# weightmeter.net
KiCad netlist of a schematic drawn in EAGLE
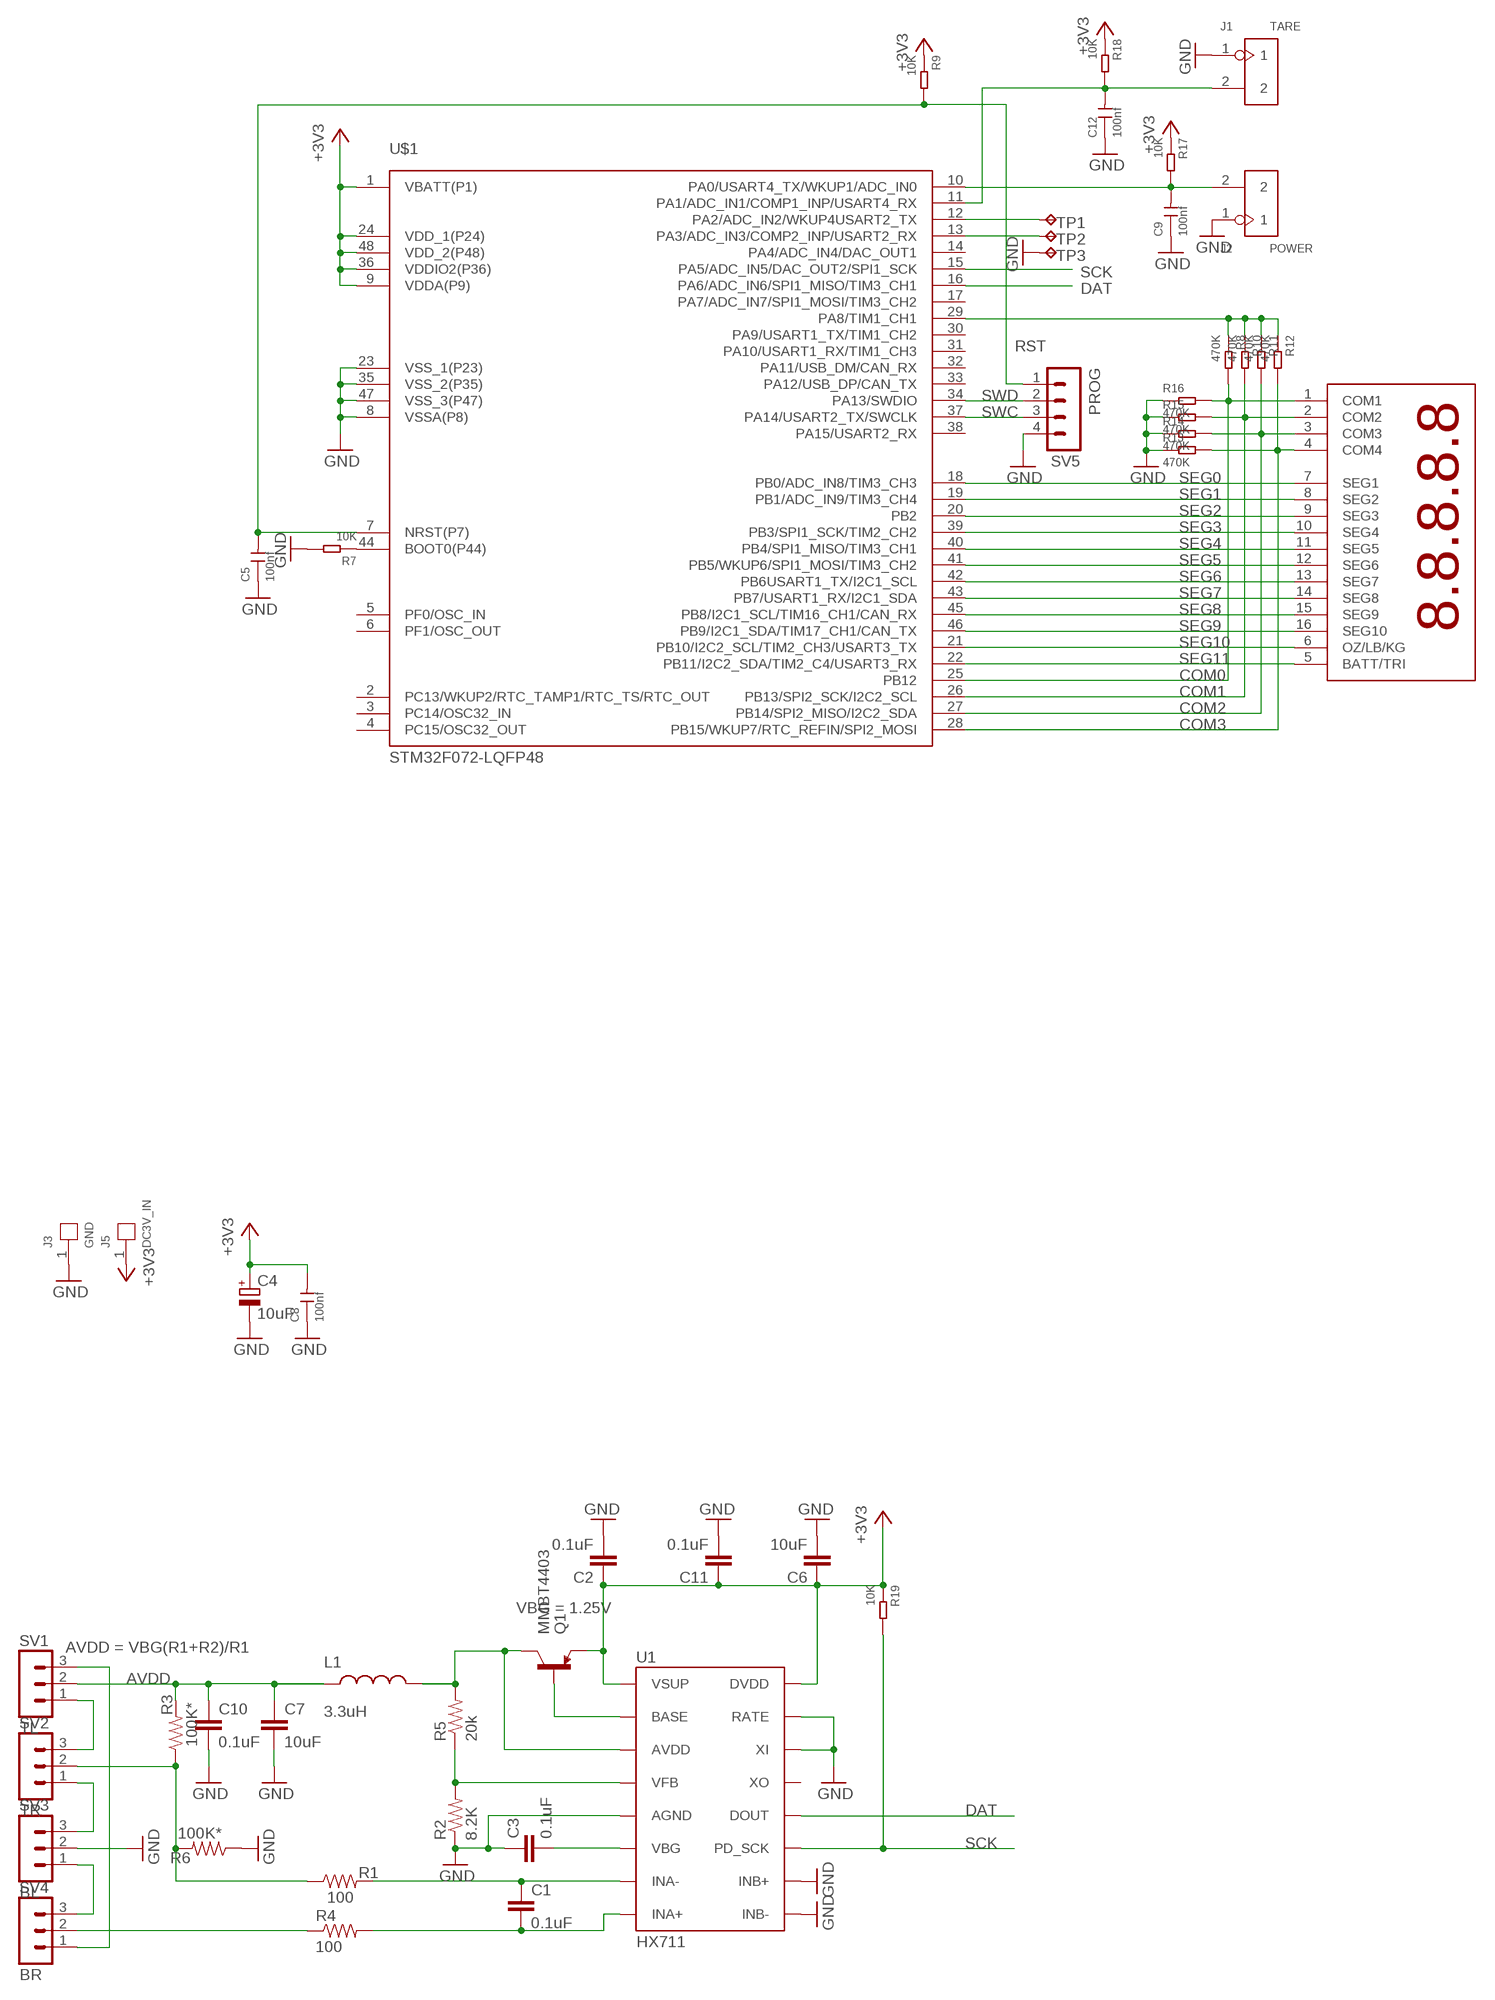
[diagram p0: schematic, sheet 1]

(export (version "E")
  (design (tool "Eeschema 10.0.6"))
  (components
    (comp (ref "C1")
      (value "0.1uF")
      (footprint "eagle-import:0603-CAP")
      (libsource (lib "eagle-import") (part "0.1UF-25V-5%(0603)"))
    )
    (comp (ref "C2")
      (value "0.1uF")
      (footprint "eagle-import:0603-CAP")
      (libsource (lib "eagle-import") (part "0.1UF-25V-5%(0603)"))
    )
    (comp (ref "C3")
      (value "0.1uF")
      (footprint "eagle-import:0603-CAP")
      (libsource (lib "eagle-import") (part "0.1UF-25V-5%(0603)"))
    )
    (comp (ref "C4")
      (value "10uF")
      (footprint "eagle-import:A_3216-18R")
      (libsource (lib "eagle-import") (part "CPOL-EUA/3216-18R"))
    )
    (comp (ref "C5")
      (value "100nf")
      (footprint "eagle-import:C0805")
      (fields (field (name "MPN") "CC0805KRX7R9BB104"))
      (libsource (lib "eagle-import") (part "CERAMIC-100NF-50V-10%-X7R(0805)"))
    )
    (comp (ref "C6")
      (value "10uF")
      (footprint "eagle-import:1210")
      (libsource (lib "eagle-import") (part "10UF50V20%(1210)"))
    )
    (comp (ref "C7")
      (value "10uF")
      (footprint "eagle-import:1210")
      (libsource (lib "eagle-import") (part "10UF50V20%(1210)"))
    )
    (comp (ref "C8")
      (value "100nf")
      (footprint "eagle-import:C0805")
      (fields (field (name "MPN") "CC0805KRX7R9BB104"))
      (libsource (lib "eagle-import") (part "CERAMIC-100NF-50V-10%-X7R(0805)"))
    )
    (comp (ref "C9")
      (value "100nf")
      (footprint "eagle-import:C0805")
      (fields (field (name "MPN") "CC0805KRX7R9BB104"))
      (libsource (lib "eagle-import") (part "CERAMIC-100NF-50V-10%-X7R(0805)"))
    )
    (comp (ref "C10")
      (value "0.1uF")
      (footprint "eagle-import:0603-CAP")
      (libsource (lib "eagle-import") (part "0.1UF-25V-5%(0603)"))
    )
    (comp (ref "C11")
      (value "0.1uF")
      (footprint "eagle-import:0603-CAP")
      (libsource (lib "eagle-import") (part "0.1UF-25V-5%(0603)"))
    )
    (comp (ref "C12")
      (value "100nf")
      (footprint "eagle-import:C0805")
      (fields (field (name "MPN") "CC0805KRX7R9BB104"))
      (libsource (lib "eagle-import") (part "CERAMIC-100NF-50V-10%-X7R(0805)"))
    )
    (comp (ref "J1")
      (value "TARE")
      (footprint "eagle-import:H2-2.54")
      (fields (field (name "MPN") "F185-1102A1BSYA1"))
      (libsource (lib "eagle-import") (part "DIP-BLACK-FEMALE-HEADER-VERT(2P-2.54)"))
    )
    (comp (ref "J2")
      (value "POWER")
      (footprint "eagle-import:H2-2.54")
      (fields (field (name "MPN") "F185-1102A1BSYA1"))
      (libsource (lib "eagle-import") (part "DIP-BLACK-FEMALE-HEADER-VERT(2P-2.54)"))
    )
    (comp (ref "J3")
      (value "GND")
      (footprint "eagle-import:1P-65_35MIL")
      (fields (field (name "MPN") "RF130-1013BBS0741"))
      (libsource (lib "eagle-import") (part "DIP-BLACK-ROUND-FEMALE-HEADER-VERT(1P-2.54)"))
    )
    (comp (ref "J5")
      (value "DC3V_IN")
      (footprint "eagle-import:1P-65_35MIL")
      (fields (field (name "MPN") "RF130-1013BBS0741"))
      (libsource (lib "eagle-import") (part "DIP-BLACK-ROUND-FEMALE-HEADER-VERT(1P-2.54)"))
    )
    (comp (ref "L1")
      (value "3.3uH")
      (footprint "eagle-import:0805")
      (libsource (lib "eagle-import") (part "INDUCTOR0805-IND"))
    )
    (comp (ref "Q1")
      (value "MMBT4403")
      (footprint "eagle-import:SOT23-3")
      (libsource (lib "eagle-import") (part "TRANSISTOR_PNPMMBT4403"))
    )
    (comp (ref "R1")
      (value "100")
      (footprint "eagle-import:0603-RES")
      (libsource (lib "eagle-import") (part "100OHM-1/10W-1%(0603)"))
    )
    (comp (ref "R2")
      (value "8.2K")
      (footprint "eagle-import:0603-RES")
      (libsource (lib "eagle-import") (part "8.2KOHM-1/10W-5%(0603)"))
    )
    (comp (ref "R3")
      (value "100K*")
      (footprint "eagle-import:0603-RES")
      (libsource (lib "eagle-import") (part "100OHM-1/10W-1%(0603)"))
    )
    (comp (ref "R4")
      (value "100")
      (footprint "eagle-import:0603-RES")
      (libsource (lib "eagle-import") (part "100OHM-1/10W-1%(0603)"))
    )
    (comp (ref "R5")
      (value "20k")
      (footprint "eagle-import:0603-RES")
      (libsource (lib "eagle-import") (part "20KOHM1/10W1%(0603)"))
    )
    (comp (ref "R6")
      (value "100K*")
      (footprint "eagle-import:0603-RES")
      (libsource (lib "eagle-import") (part "100OHM-1/10W-1%(0603)"))
    )
    (comp (ref "R7")
      (value "10K")
      (footprint "eagle-import:R0805")
      (fields (field (name "MPN") "RC0805JR-070RL"))
      (libsource (lib "eagle-import") (part "SMD-RES-0R-5%-1/8W(0805)"))
    )
    (comp (ref "R8")
      (value "470K")
      (footprint "eagle-import:R0805")
      (fields (field (name "MPN") "RC0805JR-070RL"))
      (libsource (lib "eagle-import") (part "SMD-RES-0R-5%-1/8W(0805)"))
    )
    (comp (ref "R9")
      (value "10K")
      (footprint "eagle-import:R0805")
      (fields (field (name "MPN") "RC0805JR-070RL"))
      (libsource (lib "eagle-import") (part "SMD-RES-0R-5%-1/8W(0805)"))
    )
    (comp (ref "R10")
      (value "470K")
      (footprint "eagle-import:R0805")
      (fields (field (name "MPN") "RC0805JR-070RL"))
      (libsource (lib "eagle-import") (part "SMD-RES-0R-5%-1/8W(0805)"))
    )
    (comp (ref "R11")
      (value "470K")
      (footprint "eagle-import:R0805")
      (fields (field (name "MPN") "RC0805JR-070RL"))
      (libsource (lib "eagle-import") (part "SMD-RES-0R-5%-1/8W(0805)"))
    )
    (comp (ref "R12")
      (value "470K")
      (footprint "eagle-import:R0805")
      (fields (field (name "MPN") "RC0805JR-070RL"))
      (libsource (lib "eagle-import") (part "SMD-RES-0R-5%-1/8W(0805)"))
    )
    (comp (ref "R13")
      (value "470K")
      (footprint "eagle-import:R0805")
      (fields (field (name "MPN") "RC0805JR-070RL"))
      (libsource (lib "eagle-import") (part "SMD-RES-0R-5%-1/8W(0805)"))
    )
    (comp (ref "R14")
      (value "470K")
      (footprint "eagle-import:R0805")
      (fields (field (name "MPN") "RC0805JR-070RL"))
      (libsource (lib "eagle-import") (part "SMD-RES-0R-5%-1/8W(0805)"))
    )
    (comp (ref "R15")
      (value "470K")
      (footprint "eagle-import:R0805")
      (fields (field (name "MPN") "RC0805JR-070RL"))
      (libsource (lib "eagle-import") (part "SMD-RES-0R-5%-1/8W(0805)"))
    )
    (comp (ref "R16")
      (value "470K")
      (footprint "eagle-import:R0805")
      (fields (field (name "MPN") "RC0805JR-070RL"))
      (libsource (lib "eagle-import") (part "SMD-RES-0R-5%-1/8W(0805)"))
    )
    (comp (ref "R17")
      (value "10K")
      (footprint "eagle-import:R0805")
      (fields (field (name "MPN") "RC0805JR-070RL"))
      (libsource (lib "eagle-import") (part "SMD-RES-0R-5%-1/8W(0805)"))
    )
    (comp (ref "R18")
      (value "10K")
      (footprint "eagle-import:R0805")
      (fields (field (name "MPN") "RC0805JR-070RL"))
      (libsource (lib "eagle-import") (part "SMD-RES-0R-5%-1/8W(0805)"))
    )
    (comp (ref "R19")
      (value "10K")
      (footprint "eagle-import:R0805")
      (fields (field (name "MPN") "RC0805JR-070RL"))
      (libsource (lib "eagle-import") (part "SMD-RES-0R-5%-1/8W(0805)"))
    )
    (comp (ref "SV1")
      (value "TL")
      (footprint "eagle-import:MA03-1")
      (libsource (lib "eagle-import") (part "MA03-1"))
    )
    (comp (ref "SV2")
      (value "TR")
      (footprint "eagle-import:MA03-1")
      (libsource (lib "eagle-import") (part "MA03-1"))
    )
    (comp (ref "SV3")
      (value "BL")
      (footprint "eagle-import:MA03-1")
      (libsource (lib "eagle-import") (part "MA03-1"))
    )
    (comp (ref "SV4")
      (value "BR")
      (footprint "eagle-import:MA03-1")
      (libsource (lib "eagle-import") (part "MA03-1"))
    )
    (comp (ref "SV5")
      (value "PROG")
      (footprint "eagle-import:MA04-1")
      (libsource (lib "eagle-import") (part "MA04-1"))
    )
    (comp (ref "TP1")
      (value "UART_OUT")
      (footprint "eagle-import:B1,27")
      (libsource (lib "eagle-import") (part "TPB1,27"))
    )
    (comp (ref "TP2")
      (value "UART_OUT")
      (footprint "eagle-import:B1,27")
      (libsource (lib "eagle-import") (part "TPB1,27"))
    )
    (comp (ref "TP3")
      (value "UART_OUT")
      (footprint "eagle-import:B1,27")
      (libsource (lib "eagle-import") (part "TPB1,27"))
    )
    (comp (ref "U$1")
      (value "STM32F072-LQFP48")
      (footprint "eagle-import:LQFP48")
      (libsource (lib "eagle-import") (part "STM32F072-LQFP48"))
    )
    (comp (ref "U1")
      (value "HX711")
      (footprint "eagle-import:SO16")
      (libsource (lib "eagle-import") (part "HX711HX711"))
    )
    (comp (ref "X1")
      (value "1296-T08")
      (footprint "eagle-import:1296-08")
      (libsource (lib "eagle-import") (part "1296-T08"))
    )
  )
  (nets
    (net (code "1") (name "+3V3") (class "Default")
      (node (ref "C11") (pin "1") (pinfunction "1_1") (pintype "passive"))
      (node (ref "C2") (pin "1") (pinfunction "1_1") (pintype "passive"))
      (node (ref "C4") (pin "+") (pinfunction "+_+") (pintype "passive"))
      (node (ref "C6") (pin "1") (pinfunction "1_1") (pintype "passive"))
      (node (ref "C8") (pin "2") (pinfunction "2_2") (pintype "passive"))
      (node (ref "J5") (pin "1") (pinfunction "1_1") (pintype "bidirectional"))
      (node (ref "Q1") (pin "2") (pinfunction "E_2") (pintype "passive"))
      (node (ref "R17") (pin "1") (pinfunction "1_1") (pintype "passive"))
      (node (ref "R18") (pin "1") (pinfunction "1_1") (pintype "passive"))
      (node (ref "R19") (pin "1") (pinfunction "1_1") (pintype "passive"))
      (node (ref "R9") (pin "1") (pinfunction "1_1") (pintype "passive"))
      (node (ref "U$1") (pin "1") (pinfunction "VBATT(P1)_1") (pintype "bidirectional"))
      (node (ref "U$1") (pin "24") (pinfunction "VDD_1(P24)_24") (pintype "bidirectional"))
      (node (ref "U$1") (pin "36") (pinfunction "VDDIO2(P36)_36") (pintype "bidirectional"))
      (node (ref "U$1") (pin "48") (pinfunction "VDD_2(P48)_48") (pintype "bidirectional"))
      (node (ref "U$1") (pin "9") (pinfunction "VDDA(P9)_9") (pintype "bidirectional"))
      (node (ref "U1") (pin "1") (pinfunction "VSUP_1") (pintype "bidirectional"))
      (node (ref "U1") (pin "16") (pinfunction "DVDD_16") (pintype "bidirectional"))
    )
    (net (code "2") (name "/AVDD") (class "Default")
      (node (ref "C10") (pin "1") (pinfunction "1_1") (pintype "passive"))
      (node (ref "C7") (pin "1") (pinfunction "1_1") (pintype "passive"))
      (node (ref "L1") (pin "1") (pinfunction "1_1") (pintype "passive"))
      (node (ref "R3") (pin "2") (pinfunction "2_2") (pintype "passive"))
      (node (ref "SV1") (pin "2") (pinfunction "2_2") (pintype "passive"))
    )
    (net (code "3") (name "/COM0") (class "Default")
      (node (ref "R16") (pin "2") (pinfunction "2_2") (pintype "passive"))
      (node (ref "R8") (pin "2") (pinfunction "2_2") (pintype "passive"))
      (node (ref "U$1") (pin "25") (pinfunction "PB12_25") (pintype "bidirectional"))
      (node (ref "X1") (pin "1") (pinfunction "COM1_1") (pintype "bidirectional"))
    )
    (net (code "4") (name "/COM1") (class "Default")
      (node (ref "R10") (pin "2") (pinfunction "2_2") (pintype "passive"))
      (node (ref "R15") (pin "2") (pinfunction "2_2") (pintype "passive"))
      (node (ref "U$1") (pin "26") (pinfunction "PB13/SPI2_SCK/I2C2_SCL_26") (pintype "bidirectional"))
      (node (ref "X1") (pin "2") (pinfunction "COM2_2") (pintype "bidirectional"))
    )
    (net (code "5") (name "/COM2") (class "Default")
      (node (ref "R11") (pin "2") (pinfunction "2_2") (pintype "passive"))
      (node (ref "R14") (pin "2") (pinfunction "2_2") (pintype "passive"))
      (node (ref "U$1") (pin "27") (pinfunction "PB14/SPI2_MISO/I2C2_SDA_27") (pintype "bidirectional"))
      (node (ref "X1") (pin "3") (pinfunction "COM3_3") (pintype "bidirectional"))
    )
    (net (code "6") (name "/COM3") (class "Default")
      (node (ref "R12") (pin "2") (pinfunction "2_2") (pintype "passive"))
      (node (ref "R13") (pin "2") (pinfunction "2_2") (pintype "passive"))
      (node (ref "U$1") (pin "28") (pinfunction "PB15/WKUP7/RTC_REFIN/SPI2_MOSI_28") (pintype "bidirectional"))
      (node (ref "X1") (pin "4") (pinfunction "COM4_4") (pintype "bidirectional"))
    )
    (net (code "7") (name "/DAT") (class "Default")
      (node (ref "U$1") (pin "16") (pinfunction "PA6/ADC_IN6/SPI1_MISO/TIM3_CH1_16") (pintype "bidirectional"))
      (node (ref "U1") (pin "12") (pinfunction "DOUT_12") (pintype "bidirectional"))
    )
    (net (code "8") (name "/RST") (class "Default")
      (node (ref "C5") (pin "2") (pinfunction "2_2") (pintype "passive"))
      (node (ref "R9") (pin "2") (pinfunction "2_2") (pintype "passive"))
      (node (ref "SV5") (pin "1") (pinfunction "1_1") (pintype "passive"))
      (node (ref "U$1") (pin "7") (pinfunction "NRST(P7)_7") (pintype "bidirectional"))
    )
    (net (code "9") (name "/SCK") (class "Default")
      (node (ref "R19") (pin "2") (pinfunction "2_2") (pintype "passive"))
      (node (ref "U$1") (pin "15") (pinfunction "PA5/ADC_IN5/DAC_OUT2/SPI1_SCK_15") (pintype "bidirectional"))
      (node (ref "U1") (pin "11") (pinfunction "PD_SCK_11") (pintype "bidirectional"))
    )
    (net (code "10") (name "/SEG0") (class "Default")
      (node (ref "U$1") (pin "18") (pinfunction "PB0/ADC_IN8/TIM3_CH3_18") (pintype "bidirectional"))
      (node (ref "X1") (pin "7") (pinfunction "SEG1_7") (pintype "bidirectional"))
    )
    (net (code "11") (name "/SEG1") (class "Default")
      (node (ref "U$1") (pin "19") (pinfunction "PB1/ADC_IN9/TIM3_CH4_19") (pintype "bidirectional"))
      (node (ref "X1") (pin "8") (pinfunction "SEG2_8") (pintype "bidirectional"))
    )
    (net (code "12") (name "/SEG2") (class "Default")
      (node (ref "U$1") (pin "20") (pinfunction "PB2_20") (pintype "bidirectional"))
      (node (ref "X1") (pin "9") (pinfunction "SEG3_9") (pintype "bidirectional"))
    )
    (net (code "13") (name "/SEG3") (class "Default")
      (node (ref "U$1") (pin "39") (pinfunction "PB3/SPI1_SCK/TIM2_CH2_39") (pintype "bidirectional"))
      (node (ref "X1") (pin "10") (pinfunction "SEG4_10") (pintype "bidirectional"))
    )
    (net (code "14") (name "/SEG4") (class "Default")
      (node (ref "U$1") (pin "40") (pinfunction "PB4/SPI1_MISO/TIM3_CH1_40") (pintype "bidirectional"))
      (node (ref "X1") (pin "11") (pinfunction "SEG5_11") (pintype "bidirectional"))
    )
    (net (code "15") (name "/SEG5") (class "Default")
      (node (ref "U$1") (pin "41") (pinfunction "PB5/WKUP6/SPI1_MOSI/TIM3_CH2_41") (pintype "bidirectional"))
      (node (ref "X1") (pin "12") (pinfunction "SEG6_12") (pintype "bidirectional"))
    )
    (net (code "16") (name "/SEG6") (class "Default")
      (node (ref "U$1") (pin "42") (pinfunction "PB6USART1_TX/I2C1_SCL_42") (pintype "bidirectional"))
      (node (ref "X1") (pin "13") (pinfunction "SEG7_13") (pintype "bidirectional"))
    )
    (net (code "17") (name "/SEG7") (class "Default")
      (node (ref "U$1") (pin "43") (pinfunction "PB7/USART1_RX/I2C1_SDA_43") (pintype "bidirectional"))
      (node (ref "X1") (pin "14") (pinfunction "SEG8_14") (pintype "bidirectional"))
    )
    (net (code "18") (name "/SEG8") (class "Default")
      (node (ref "U$1") (pin "45") (pinfunction "PB8/I2C1_SCL/TIM16_CH1/CAN_RX_45") (pintype "bidirectional"))
      (node (ref "X1") (pin "15") (pinfunction "SEG9_15") (pintype "bidirectional"))
    )
    (net (code "19") (name "/SEG9") (class "Default")
      (node (ref "U$1") (pin "46") (pinfunction "PB9/I2C1_SDA/TIM17_CH1/CAN_TX_46") (pintype "bidirectional"))
      (node (ref "X1") (pin "16") (pinfunction "SEG10_16") (pintype "bidirectional"))
    )
    (net (code "20") (name "/SEG10") (class "Default")
      (node (ref "U$1") (pin "21") (pinfunction "PB10/I2C2_SCL/TIM2_CH3/USART3_TX_21") (pintype "bidirectional"))
      (node (ref "X1") (pin "6") (pinfunction "OZ/LB/KG_6") (pintype "bidirectional"))
    )
    (net (code "21") (name "/SEG11") (class "Default")
      (node (ref "U$1") (pin "22") (pinfunction "PB11/I2C2_SDA/TIM2_C4/USART3_RX_22") (pintype "bidirectional"))
      (node (ref "X1") (pin "5") (pinfunction "BATT/TRI_5") (pintype "bidirectional"))
    )
    (net (code "22") (name "/SWC") (class "Default")
      (node (ref "SV5") (pin "3") (pinfunction "3_3") (pintype "passive"))
      (node (ref "U$1") (pin "37") (pinfunction "PA14/USART2_TX/SWCLK_37") (pintype "bidirectional"))
    )
    (net (code "23") (name "/SWD") (class "Default")
      (node (ref "SV5") (pin "2") (pinfunction "2_2") (pintype "passive"))
      (node (ref "U$1") (pin "34") (pinfunction "PA13/SWDIO_34") (pintype "bidirectional"))
    )
    (net (code "24") (name "GND") (class "Default")
      (node (ref "C10") (pin "2") (pinfunction "2_2") (pintype "passive"))
      (node (ref "C11") (pin "2") (pinfunction "2_2") (pintype "passive"))
      (node (ref "C12") (pin "1") (pinfunction "1_1") (pintype "passive"))
      (node (ref "C2") (pin "2") (pinfunction "2_2") (pintype "passive"))
      (node (ref "C3") (pin "1") (pinfunction "1_1") (pintype "passive"))
      (node (ref "C4") (pin "-") (pinfunction "-_-") (pintype "passive"))
      (node (ref "C5") (pin "1") (pinfunction "1_1") (pintype "passive"))
      (node (ref "C6") (pin "2") (pinfunction "2_2") (pintype "passive"))
      (node (ref "C7") (pin "2") (pinfunction "2_2") (pintype "passive"))
      (node (ref "C8") (pin "1") (pinfunction "1_1") (pintype "passive"))
      (node (ref "C9") (pin "1") (pinfunction "1_1") (pintype "passive"))
      (node (ref "J1") (pin "1") (pinfunction "1_1") (pintype "bidirectional"))
      (node (ref "J2") (pin "1") (pinfunction "1_1") (pintype "bidirectional"))
      (node (ref "J3") (pin "1") (pinfunction "1_1") (pintype "bidirectional"))
      (node (ref "R13") (pin "1") (pinfunction "1_1") (pintype "passive"))
      (node (ref "R14") (pin "1") (pinfunction "1_1") (pintype "passive"))
      (node (ref "R15") (pin "1") (pinfunction "1_1") (pintype "passive"))
      (node (ref "R16") (pin "1") (pinfunction "1_1") (pintype "passive"))
      (node (ref "R2") (pin "1") (pinfunction "1_1") (pintype "passive"))
      (node (ref "R6") (pin "1") (pinfunction "1_1") (pintype "passive"))
      (node (ref "R7") (pin "2") (pinfunction "2_2") (pintype "passive"))
      (node (ref "SV3") (pin "2") (pinfunction "2_2") (pintype "passive"))
      (node (ref "SV5") (pin "4") (pinfunction "4_4") (pintype "passive"))
      (node (ref "TP3") (pin "TP") (pinfunction "TP_TP") (pintype "input"))
      (node (ref "U$1") (pin "23") (pinfunction "VSS_1(P23)_23") (pintype "bidirectional"))
      (node (ref "U$1") (pin "35") (pinfunction "VSS_2(P35)_35") (pintype "bidirectional"))
      (node (ref "U$1") (pin "47") (pinfunction "VSS_3(P47)_47") (pintype "bidirectional"))
      (node (ref "U$1") (pin "8") (pinfunction "VSSA(P8)_8") (pintype "bidirectional"))
      (node (ref "U1") (pin "10") (pinfunction "INB+_10") (pintype "bidirectional"))
      (node (ref "U1") (pin "14") (pinfunction "XI_14") (pintype "bidirectional"))
      (node (ref "U1") (pin "15") (pinfunction "RATE_15") (pintype "bidirectional"))
      (node (ref "U1") (pin "5") (pinfunction "AGND_5") (pintype "bidirectional"))
      (node (ref "U1") (pin "9") (pinfunction "INB-_9") (pintype "bidirectional"))
    )
    (net (code "25") (name "Net-(Q1-B)") (class "Default")
      (node (ref "Q1") (pin "1") (pinfunction "B_1") (pintype "passive"))
      (node (ref "U1") (pin "2") (pinfunction "BASE_2") (pintype "bidirectional"))
    )
    (net (code "26") (name "Net-(Q1-C)") (class "Default")
      (node (ref "L1") (pin "2") (pinfunction "2_2") (pintype "passive"))
      (node (ref "Q1") (pin "3") (pinfunction "C_3") (pintype "passive"))
      (node (ref "R5") (pin "2") (pinfunction "2_2") (pintype "passive"))
      (node (ref "U1") (pin "3") (pinfunction "AVDD_3") (pintype "bidirectional"))
    )
    (net (code "27") (name "Net-(R1-Pad1)") (class "Default")
      (node (ref "R1") (pin "1") (pinfunction "1_1") (pintype "passive"))
      (node (ref "R3") (pin "1") (pinfunction "1_1") (pintype "passive"))
      (node (ref "R6") (pin "2") (pinfunction "2_2") (pintype "passive"))
      (node (ref "SV2") (pin "2") (pinfunction "2_2") (pintype "passive"))
    )
    (net (code "28") (name "Net-(R4-Pad1)") (class "Default")
      (node (ref "R4") (pin "1") (pinfunction "1_1") (pintype "passive"))
      (node (ref "SV4") (pin "2") (pinfunction "2_2") (pintype "passive"))
    )
    (net (code "29") (name "Net-(SV1-Pad1)") (class "Default")
      (node (ref "SV1") (pin "1") (pinfunction "1_1") (pintype "passive"))
      (node (ref "SV2") (pin "3") (pinfunction "3_3") (pintype "passive"))
    )
    (net (code "30") (name "Net-(SV1-Pad3)") (class "Default")
      (node (ref "SV1") (pin "3") (pinfunction "3_3") (pintype "passive"))
      (node (ref "SV4") (pin "1") (pinfunction "1_1") (pintype "passive"))
    )
    (net (code "31") (name "Net-(SV2-Pad1)") (class "Default")
      (node (ref "SV2") (pin "1") (pinfunction "1_1") (pintype "passive"))
      (node (ref "SV3") (pin "3") (pinfunction "3_3") (pintype "passive"))
    )
    (net (code "32") (name "Net-(SV3-Pad1)") (class "Default")
      (node (ref "SV3") (pin "1") (pinfunction "1_1") (pintype "passive"))
      (node (ref "SV4") (pin "3") (pinfunction "3_3") (pintype "passive"))
    )
    (net (code "33") (name "Net-(U$1-BOOT0(P44))") (class "Default")
      (node (ref "R7") (pin "1") (pinfunction "1_1") (pintype "passive"))
      (node (ref "U$1") (pin "44") (pinfunction "BOOT0(P44)_44") (pintype "bidirectional"))
    )
    (net (code "34") (name "Net-(U$1-PA0{slash}USART4_TX{slash}WKUP1{slash}ADC_IN0)") (class "Default")
      (node (ref "C9") (pin "2") (pinfunction "2_2") (pintype "passive"))
      (node (ref "J2") (pin "2") (pinfunction "2_2") (pintype "bidirectional"))
      (node (ref "R17") (pin "2") (pinfunction "2_2") (pintype "passive"))
      (node (ref "U$1") (pin "10") (pinfunction "PA0/USART4_TX/WKUP1/ADC_IN0_10") (pintype "bidirectional"))
    )
    (net (code "35") (name "Net-(U$1-PA1{slash}ADC_IN1{slash}COMP1_INP{slash}USART4_RX)") (class "Default")
      (node (ref "C12") (pin "2") (pinfunction "2_2") (pintype "passive"))
      (node (ref "J1") (pin "2") (pinfunction "2_2") (pintype "bidirectional"))
      (node (ref "R18") (pin "2") (pinfunction "2_2") (pintype "passive"))
      (node (ref "U$1") (pin "11") (pinfunction "PA1/ADC_IN1/COMP1_INP/USART4_RX_11") (pintype "bidirectional"))
    )
    (net (code "36") (name "Net-(U$1-PA2{slash}ADC_IN2{slash}WKUP4USART2_TX)") (class "Default")
      (node (ref "TP1") (pin "TP") (pinfunction "TP_TP") (pintype "input"))
      (node (ref "U$1") (pin "12") (pinfunction "PA2/ADC_IN2/WKUP4USART2_TX_12") (pintype "bidirectional"))
    )
    (net (code "37") (name "Net-(U$1-PA3{slash}ADC_IN3{slash}COMP2_INP{slash}USART2_RX)") (class "Default")
      (node (ref "TP2") (pin "TP") (pinfunction "TP_TP") (pintype "input"))
      (node (ref "U$1") (pin "13") (pinfunction "PA3/ADC_IN3/COMP2_INP/USART2_RX_13") (pintype "bidirectional"))
    )
    (net (code "38") (name "Net-(U$1-PA8{slash}TIM1_CH1)") (class "Default")
      (node (ref "R10") (pin "1") (pinfunction "1_1") (pintype "passive"))
      (node (ref "R11") (pin "1") (pinfunction "1_1") (pintype "passive"))
      (node (ref "R12") (pin "1") (pinfunction "1_1") (pintype "passive"))
      (node (ref "R8") (pin "1") (pinfunction "1_1") (pintype "passive"))
      (node (ref "U$1") (pin "29") (pinfunction "PA8/TIM1_CH1_29") (pintype "bidirectional"))
    )
    (net (code "39") (name "Net-(U1-INA+)") (class "Default")
      (node (ref "C1") (pin "2") (pinfunction "2_2") (pintype "passive"))
      (node (ref "R4") (pin "2") (pinfunction "2_2") (pintype "passive"))
      (node (ref "U1") (pin "8") (pinfunction "INA+_8") (pintype "bidirectional"))
    )
    (net (code "40") (name "Net-(U1-INA-)") (class "Default")
      (node (ref "C1") (pin "1") (pinfunction "1_1") (pintype "passive"))
      (node (ref "R1") (pin "2") (pinfunction "2_2") (pintype "passive"))
      (node (ref "U1") (pin "7") (pinfunction "INA-_7") (pintype "bidirectional"))
    )
    (net (code "41") (name "Net-(U1-VBG)") (class "Default")
      (node (ref "C3") (pin "2") (pinfunction "2_2") (pintype "passive"))
      (node (ref "U1") (pin "6") (pinfunction "VBG_6") (pintype "bidirectional"))
    )
    (net (code "42") (name "Net-(U1-VFB)") (class "Default")
      (node (ref "R2") (pin "2") (pinfunction "2_2") (pintype "passive"))
      (node (ref "R5") (pin "1") (pinfunction "1_1") (pintype "passive"))
      (node (ref "U1") (pin "4") (pinfunction "VFB_4") (pintype "bidirectional"))
    )
    (net (code "43") (name "unconnected-(U$1-PA4{slash}ADC_IN4{slash}DAC_OUT1-Pad14)") (class "Default")
      (node (ref "U$1") (pin "14") (pinfunction "PA4/ADC_IN4/DAC_OUT1_14") (pintype "bidirectional"))
    )
    (net (code "44") (name "unconnected-(U$1-PA7{slash}ADC_IN7{slash}SPI1_MOSI{slash}TIM3_CH2-Pad17)") (class "Default")
      (node (ref "U$1") (pin "17") (pinfunction "PA7/ADC_IN7/SPI1_MOSI/TIM3_CH2_17") (pintype "bidirectional"))
    )
    (net (code "45") (name "unconnected-(U$1-PA9{slash}USART1_TX{slash}TIM1_CH2-Pad30)") (class "Default")
      (node (ref "U$1") (pin "30") (pinfunction "PA9/USART1_TX/TIM1_CH2_30") (pintype "bidirectional"))
    )
    (net (code "46") (name "unconnected-(U$1-PA10{slash}USART1_RX{slash}TIM1_CH3-Pad31)") (class "Default")
      (node (ref "U$1") (pin "31") (pinfunction "PA10/USART1_RX/TIM1_CH3_31") (pintype "bidirectional"))
    )
    (net (code "47") (name "unconnected-(U$1-PA11{slash}USB_DM{slash}CAN_RX-Pad32)") (class "Default")
      (node (ref "U$1") (pin "32") (pinfunction "PA11/USB_DM/CAN_RX_32") (pintype "bidirectional"))
    )
    (net (code "48") (name "unconnected-(U$1-PA12{slash}USB_DP{slash}CAN_TX-Pad33)") (class "Default")
      (node (ref "U$1") (pin "33") (pinfunction "PA12/USB_DP/CAN_TX_33") (pintype "bidirectional"))
    )
    (net (code "49") (name "unconnected-(U$1-PA15{slash}USART2_RX-Pad38)") (class "Default")
      (node (ref "U$1") (pin "38") (pinfunction "PA15/USART2_RX_38") (pintype "bidirectional"))
    )
    (net (code "50") (name "unconnected-(U$1-PC13{slash}WKUP2{slash}RTC_TAMP1{slash}RTC_TS{slash}RTC_OUT-Pad2)") (class "Default")
      (node (ref "U$1") (pin "2") (pinfunction "PC13/WKUP2/RTC_TAMP1/RTC_TS/RTC_OUT_2") (pintype "bidirectional"))
    )
    (net (code "51") (name "unconnected-(U$1-PC14{slash}OSC32_IN-Pad3)") (class "Default")
      (node (ref "U$1") (pin "3") (pinfunction "PC14/OSC32_IN_3") (pintype "bidirectional"))
    )
    (net (code "52") (name "unconnected-(U$1-PC15{slash}OSC32_OUT-Pad4)") (class "Default")
      (node (ref "U$1") (pin "4") (pinfunction "PC15/OSC32_OUT_4") (pintype "bidirectional"))
    )
    (net (code "53") (name "unconnected-(U$1-PF0{slash}OSC_IN-Pad5)") (class "Default")
      (node (ref "U$1") (pin "5") (pinfunction "PF0/OSC_IN_5") (pintype "bidirectional"))
    )
    (net (code "54") (name "unconnected-(U$1-PF1{slash}OSC_OUT-Pad6)") (class "Default")
      (node (ref "U$1") (pin "6") (pinfunction "PF1/OSC_OUT_6") (pintype "bidirectional"))
    )
    (net (code "55") (name "unconnected-(U1-XO-Pad13)") (class "Default")
      (node (ref "U1") (pin "13") (pinfunction "XO_13") (pintype "bidirectional"))
    )
  )
)
